# air_cape_board_led.net
KiCad netlist of a schematic drawn in EAGLE
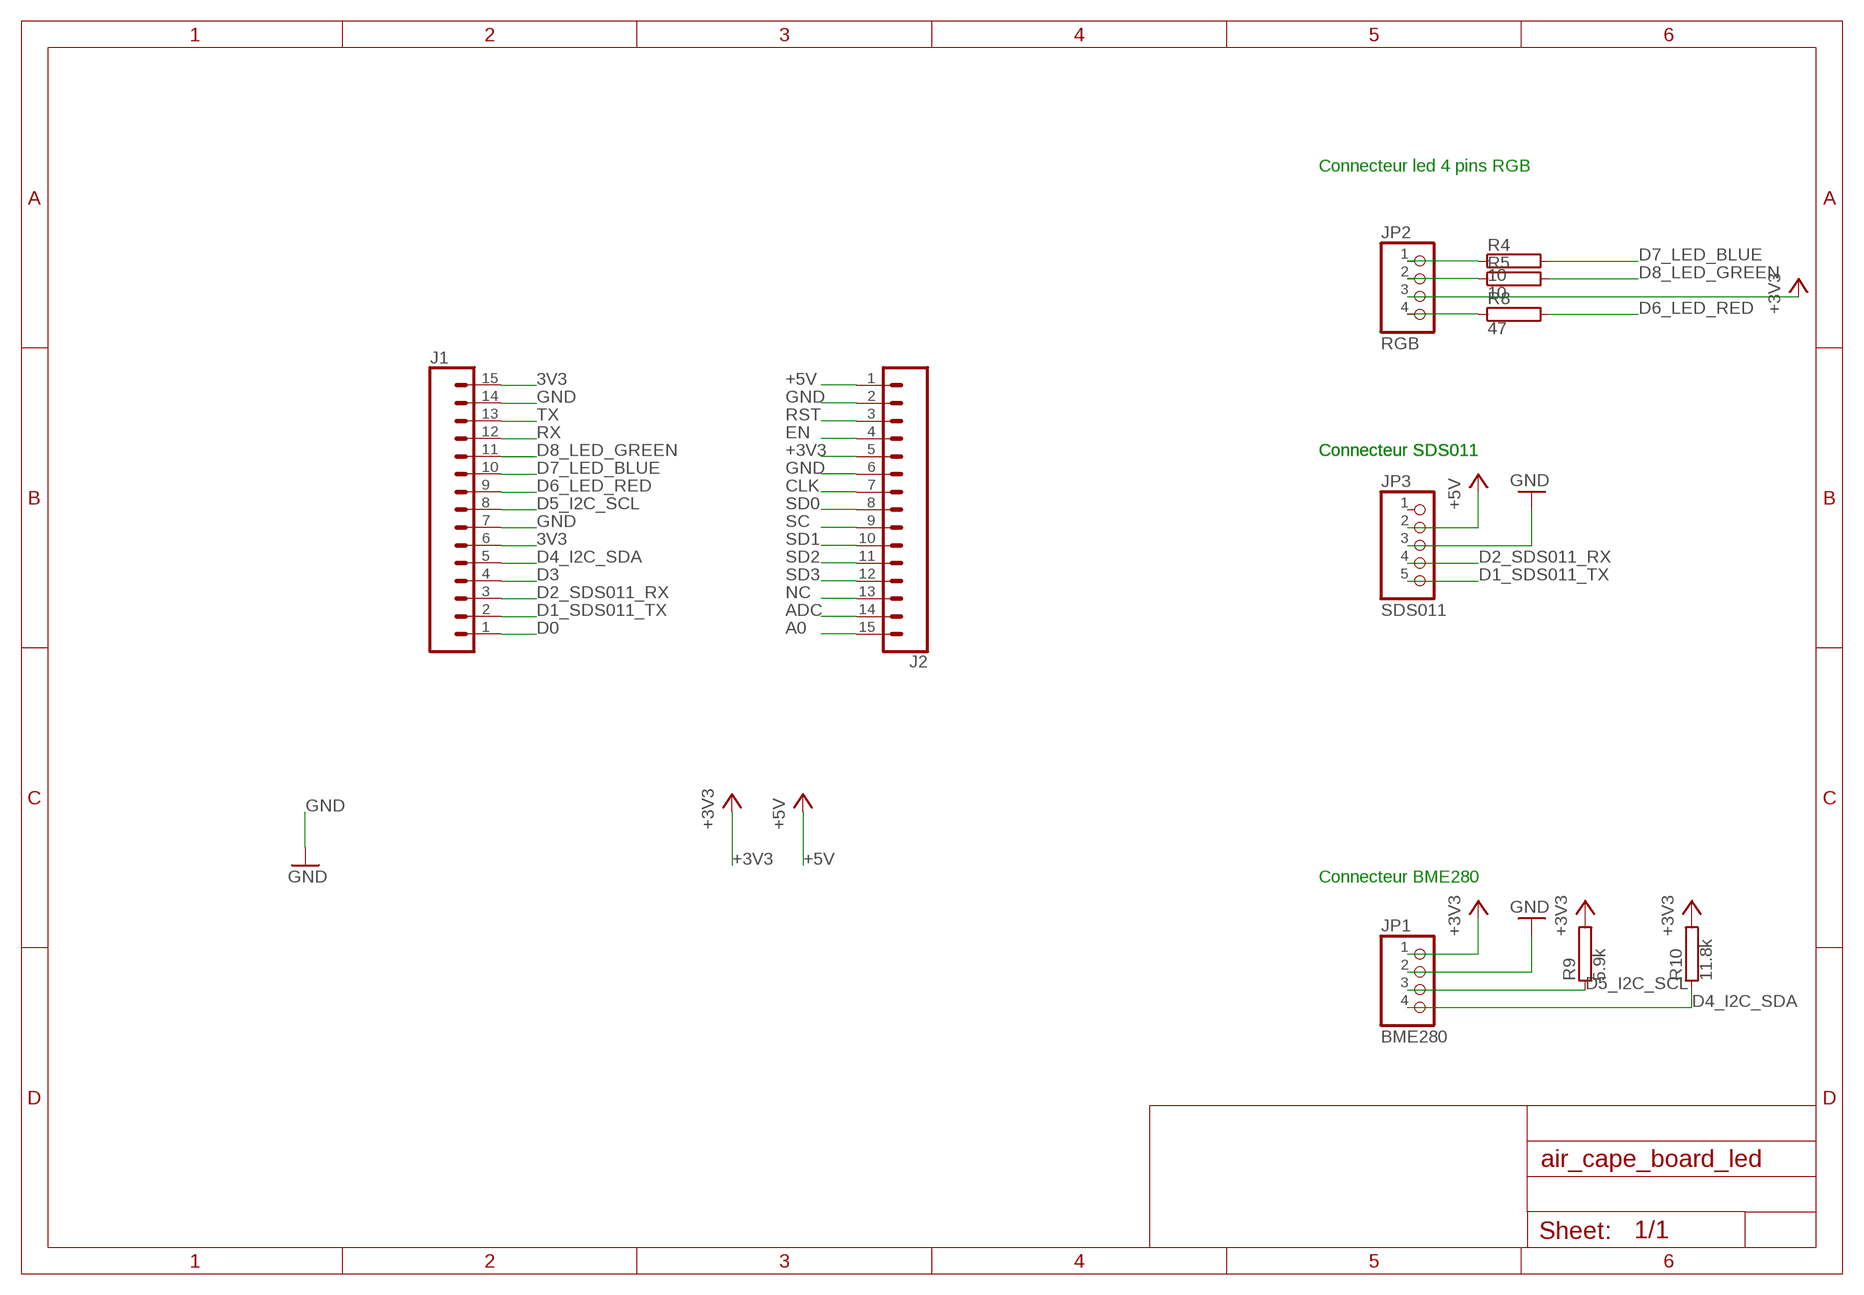
[diagram p0: schematic, sheet 1]

(export (version "E")
  (design (tool "Eeschema 10.0.6"))
  (components
    (comp (ref "J1")
      (value "CONN_15")
      (footprint "eagle-import:1X15")
      (libsource (lib "eagle-import") (part "CONN_15"))
    )
    (comp (ref "J2")
      (value "CONN_15")
      (footprint "eagle-import:1X15")
      (libsource (lib "eagle-import") (part "CONN_15"))
    )
    (comp (ref "JP1")
      (value "BME280")
      (footprint "eagle-import:1X04")
      (libsource (lib "eagle-import") (part "PINHD-1X4"))
    )
    (comp (ref "JP2")
      (value "RGB")
      (footprint "eagle-import:1X04")
      (libsource (lib "eagle-import") (part "PINHD-1X4"))
    )
    (comp (ref "JP3")
      (value "SDS011")
      (footprint "eagle-import:1X05")
      (libsource (lib "eagle-import") (part "PINHD-1X5"))
    )
    (comp (ref "R4")
      (value "10")
      (footprint "eagle-import:RS1_4")
      (fields (field (name "MF") "OHMITE") (field (name "MPN") "RRS1K0"))
      (libsource (lib "eagle-import") (part "RRS1/4"))
    )
    (comp (ref "R5")
      (value "10")
      (footprint "eagle-import:RS1_4")
      (fields (field (name "MF") "OHMITE") (field (name "MPN") "RRS1K0"))
      (libsource (lib "eagle-import") (part "RRS1/4"))
    )
    (comp (ref "R8")
      (value "47")
      (footprint "eagle-import:RS1_4")
      (fields (field (name "MF") "OHMITE") (field (name "MPN") "RRS1K0"))
      (libsource (lib "eagle-import") (part "RRS1/4"))
    )
    (comp (ref "R9")
      (value "5.9k")
      (footprint "eagle-import:RS1_4")
      (fields (field (name "MF") "OHMITE") (field (name "MPN") "RRS1K0"))
      (libsource (lib "eagle-import") (part "RRS1/4"))
    )
    (comp (ref "R10")
      (value "11.8k")
      (footprint "eagle-import:RS1_4")
      (fields (field (name "MF") "OHMITE") (field (name "MPN") "RRS1K0"))
      (libsource (lib "eagle-import") (part "RRS1/4"))
    )
  )
  (nets
    (net (code "1") (name "+3V3") (class "Default")
      (node (ref "J2") (pin "5") (pinfunction "5_5") (pintype "passive"))
      (node (ref "JP1") (pin "1") (pinfunction "1_1") (pintype "passive"))
      (node (ref "JP2") (pin "3") (pinfunction "3_3") (pintype "passive"))
      (node (ref "R10") (pin "2") (pinfunction "2_2") (pintype "passive"))
      (node (ref "R9") (pin "2") (pinfunction "2_2") (pintype "passive"))
    )
    (net (code "2") (name "+5V") (class "Default")
      (node (ref "J2") (pin "1") (pinfunction "1_1") (pintype "passive"))
      (node (ref "JP3") (pin "2") (pinfunction "2_2") (pintype "passive"))
    )
    (net (code "3") (name "/3V3") (class "Default")
      (node (ref "J1") (pin "15") (pinfunction "15_15") (pintype "passive"))
      (node (ref "J1") (pin "6") (pinfunction "6_6") (pintype "passive"))
    )
    (net (code "4") (name "/A0") (class "Default")
      (node (ref "J2") (pin "15") (pinfunction "15_15") (pintype "passive"))
    )
    (net (code "5") (name "/ADC") (class "Default")
      (node (ref "J2") (pin "14") (pinfunction "14_14") (pintype "passive"))
    )
    (net (code "6") (name "/CLK") (class "Default")
      (node (ref "J2") (pin "7") (pinfunction "7_7") (pintype "passive"))
    )
    (net (code "7") (name "/D0") (class "Default")
      (node (ref "J1") (pin "1") (pinfunction "1_1") (pintype "passive"))
    )
    (net (code "8") (name "/D1_SDS011_TX") (class "Default")
      (node (ref "J1") (pin "2") (pinfunction "2_2") (pintype "passive"))
      (node (ref "JP3") (pin "5") (pinfunction "5_5") (pintype "passive"))
    )
    (net (code "9") (name "/D2_SDS011_RX") (class "Default")
      (node (ref "J1") (pin "3") (pinfunction "3_3") (pintype "passive"))
      (node (ref "JP3") (pin "4") (pinfunction "4_4") (pintype "passive"))
    )
    (net (code "10") (name "/D3") (class "Default")
      (node (ref "J1") (pin "4") (pinfunction "4_4") (pintype "passive"))
    )
    (net (code "11") (name "/D4_I2C_SDA") (class "Default")
      (node (ref "J1") (pin "5") (pinfunction "5_5") (pintype "passive"))
      (node (ref "JP1") (pin "4") (pinfunction "4_4") (pintype "passive"))
      (node (ref "R10") (pin "1") (pinfunction "1_1") (pintype "passive"))
    )
    (net (code "12") (name "/D5_I2C_SCL") (class "Default")
      (node (ref "J1") (pin "8") (pinfunction "8_8") (pintype "passive"))
      (node (ref "JP1") (pin "3") (pinfunction "3_3") (pintype "passive"))
      (node (ref "R9") (pin "1") (pinfunction "1_1") (pintype "passive"))
    )
    (net (code "13") (name "/D6_LED_RED") (class "Default")
      (node (ref "J1") (pin "9") (pinfunction "9_9") (pintype "passive"))
      (node (ref "R8") (pin "2") (pinfunction "2_2") (pintype "passive"))
    )
    (net (code "14") (name "/D7_LED_BLUE") (class "Default")
      (node (ref "J1") (pin "10") (pinfunction "10_10") (pintype "passive"))
      (node (ref "R4") (pin "2") (pinfunction "2_2") (pintype "passive"))
    )
    (net (code "15") (name "/D8_LED_GREEN") (class "Default")
      (node (ref "J1") (pin "11") (pinfunction "11_11") (pintype "passive"))
      (node (ref "R5") (pin "2") (pinfunction "2_2") (pintype "passive"))
    )
    (net (code "16") (name "/EN") (class "Default")
      (node (ref "J2") (pin "4") (pinfunction "4_4") (pintype "passive"))
    )
    (net (code "17") (name "/NC") (class "Default")
      (node (ref "J2") (pin "13") (pinfunction "13_13") (pintype "passive"))
    )
    (net (code "18") (name "/RST") (class "Default")
      (node (ref "J2") (pin "3") (pinfunction "3_3") (pintype "passive"))
    )
    (net (code "19") (name "/RX") (class "Default")
      (node (ref "J1") (pin "12") (pinfunction "12_12") (pintype "passive"))
    )
    (net (code "20") (name "/SC") (class "Default")
      (node (ref "J2") (pin "9") (pinfunction "9_9") (pintype "passive"))
    )
    (net (code "21") (name "/SD0") (class "Default")
      (node (ref "J2") (pin "8") (pinfunction "8_8") (pintype "passive"))
    )
    (net (code "22") (name "/SD1") (class "Default")
      (node (ref "J2") (pin "10") (pinfunction "10_10") (pintype "passive"))
    )
    (net (code "23") (name "/SD2") (class "Default")
      (node (ref "J2") (pin "11") (pinfunction "11_11") (pintype "passive"))
    )
    (net (code "24") (name "/SD3") (class "Default")
      (node (ref "J2") (pin "12") (pinfunction "12_12") (pintype "passive"))
    )
    (net (code "25") (name "/TX") (class "Default")
      (node (ref "J1") (pin "13") (pinfunction "13_13") (pintype "passive"))
    )
    (net (code "26") (name "GND") (class "Default")
      (node (ref "J1") (pin "14") (pinfunction "14_14") (pintype "passive"))
      (node (ref "J1") (pin "7") (pinfunction "7_7") (pintype "passive"))
      (node (ref "J2") (pin "2") (pinfunction "2_2") (pintype "passive"))
      (node (ref "J2") (pin "6") (pinfunction "6_6") (pintype "passive"))
      (node (ref "JP1") (pin "2") (pinfunction "2_2") (pintype "passive"))
      (node (ref "JP3") (pin "3") (pinfunction "3_3") (pintype "passive"))
    )
    (net (code "27") (name "Net-(JP2-Pad1)") (class "Default")
      (node (ref "JP2") (pin "1") (pinfunction "1_1") (pintype "passive"))
      (node (ref "R4") (pin "1") (pinfunction "1_1") (pintype "passive"))
    )
    (net (code "28") (name "Net-(JP2-Pad2)") (class "Default")
      (node (ref "JP2") (pin "2") (pinfunction "2_2") (pintype "passive"))
      (node (ref "R5") (pin "1") (pinfunction "1_1") (pintype "passive"))
    )
    (net (code "29") (name "Net-(JP2-Pad4)") (class "Default")
      (node (ref "JP2") (pin "4") (pinfunction "4_4") (pintype "passive"))
      (node (ref "R8") (pin "1") (pinfunction "1_1") (pintype "passive"))
    )
    (net (code "30") (name "unconnected-(JP3-Pad1)") (class "Default")
      (node (ref "JP3") (pin "1") (pinfunction "1_1") (pintype "passive"))
    )
  )
)
